# TEMP_sensor.net
KiCad netlist of a schematic drawn in EAGLE
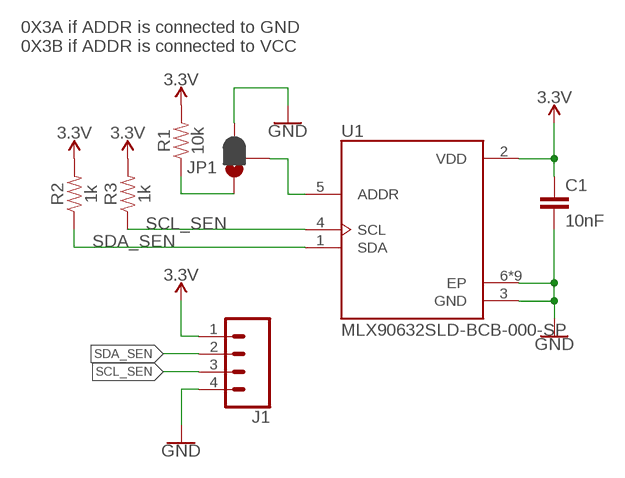
[diagram p0: schematic, sheet 1]

(export (version "E")
  (design (tool "Eeschema 10.0.6"))
  (components
    (comp (ref "C1")
      (value "10nF")
      (footprint "eagle-import:0603")
      (libsource (lib "eagle-import") (part "10NF-0603-50V-10%"))
    )
    (comp (ref "J1")
      (value "CONN_04")
      (footprint "eagle-import:1X04")
      (libsource (lib "eagle-import") (part "CONN_04"))
    )
    (comp (ref "JP1")
      (value "JUMPER-SMT_3_1-NC_PASTE_SILK")
      (footprint "eagle-import:SMT-JUMPER_3_1-NC_PASTE_SILK")
      (libsource (lib "eagle-import") (part "JUMPER-SMT_3_1-NC_PASTE_SILK"))
    )
    (comp (ref "R1")
      (value "10k")
      (footprint "eagle-import:0603")
      (libsource (lib "eagle-import") (part "10KOHM-0603-1/10W-1%"))
    )
    (comp (ref "R2")
      (value "1k")
      (footprint "eagle-import:0603")
      (libsource (lib "eagle-import") (part "1KOHM-0603-1/10W-1%"))
    )
    (comp (ref "R3")
      (value "1k")
      (footprint "eagle-import:0603")
      (libsource (lib "eagle-import") (part "1KOHM-0603-1/10W-1%"))
    )
    (comp (ref "U1")
      (value "MLX90632SLD-BCB-000-SP")
      (footprint "eagle-import:XDCR_MLX90632SLD-BCB-000-SP")
      (fields (field (name "MF") "Melexis Technologies"))
      (libsource (lib "eagle-import") (part "MLX90632SLD-BCB-000-SP"))
    )
  )
  (nets
    (net (code "1") (name "3.3V") (class "Default")
      (node (ref "C1") (pin "1") (pinfunction "1_1") (pintype "passive"))
      (node (ref "J1") (pin "1") (pinfunction "1_1") (pintype "passive"))
      (node (ref "R1") (pin "2") (pinfunction "2_2") (pintype "passive"))
      (node (ref "R2") (pin "2") (pinfunction "2_2") (pintype "passive"))
      (node (ref "R3") (pin "2") (pinfunction "2_2") (pintype "passive"))
      (node (ref "U1") (pin "2") (pinfunction "VDD_2") (pintype "power_in"))
    )
    (net (code "2") (name "GND") (class "Default")
      (node (ref "C1") (pin "2") (pinfunction "2_2") (pintype "passive"))
      (node (ref "J1") (pin "4") (pinfunction "4_4") (pintype "passive"))
      (node (ref "JP1") (pin "3") (pinfunction "3_3") (pintype "passive"))
      (node (ref "U1") (pin "3") (pinfunction "GND_3") (pintype "power_in"))
      (node (ref "U1") (pin "6") (pinfunction "EP_6") (pintype "power_in"))
      (node (ref "U1") (pin "P$1") (pinfunction "EP_P$1") (pintype "power_in"))
      (node (ref "U1") (pin "P$2") (pinfunction "EP_P$2") (pintype "power_in"))
      (node (ref "U1") (pin "P$3") (pinfunction "EP_P$3") (pintype "power_in"))
      (node (ref "U1") (pin "P$4") (pinfunction "EP_P$4") (pintype "power_in"))
      (node (ref "U1") (pin "P$5") (pinfunction "EP_P$5") (pintype "power_in"))
      (node (ref "U1") (pin "P$6") (pinfunction "EP_P$6") (pintype "power_in"))
      (node (ref "U1") (pin "P$7") (pinfunction "EP_P$7") (pintype "power_in"))
      (node (ref "U1") (pin "P$8") (pinfunction "EP_P$8") (pintype "power_in"))
    )
    (net (code "3") (name "Net-(JP1-Pad1)") (class "Default")
      (node (ref "JP1") (pin "1") (pinfunction "1_1") (pintype "passive"))
      (node (ref "R1") (pin "1") (pinfunction "1_1") (pintype "passive"))
    )
    (net (code "4") (name "Net-(U1-ADDR)") (class "Default")
      (node (ref "JP1") (pin "2") (pinfunction "2_2") (pintype "passive"))
      (node (ref "U1") (pin "5") (pinfunction "ADDR_5") (pintype "input"))
    )
    (net (code "5") (name "SCL_SEN") (class "Default")
      (node (ref "J1") (pin "3") (pinfunction "3_3") (pintype "passive"))
      (node (ref "R3") (pin "1") (pinfunction "1_1") (pintype "passive"))
      (node (ref "U1") (pin "4") (pinfunction "SCL_4") (pintype "input"))
    )
    (net (code "6") (name "SDA_SEN") (class "Default")
      (node (ref "J1") (pin "2") (pinfunction "2_2") (pintype "passive"))
      (node (ref "R2") (pin "1") (pinfunction "1_1") (pintype "passive"))
      (node (ref "U1") (pin "1") (pinfunction "SDA_1") (pintype "bidirectional"))
    )
  )
)
